# Stemma_Notecard.net
KiCad netlist of a schematic drawn in EAGLE
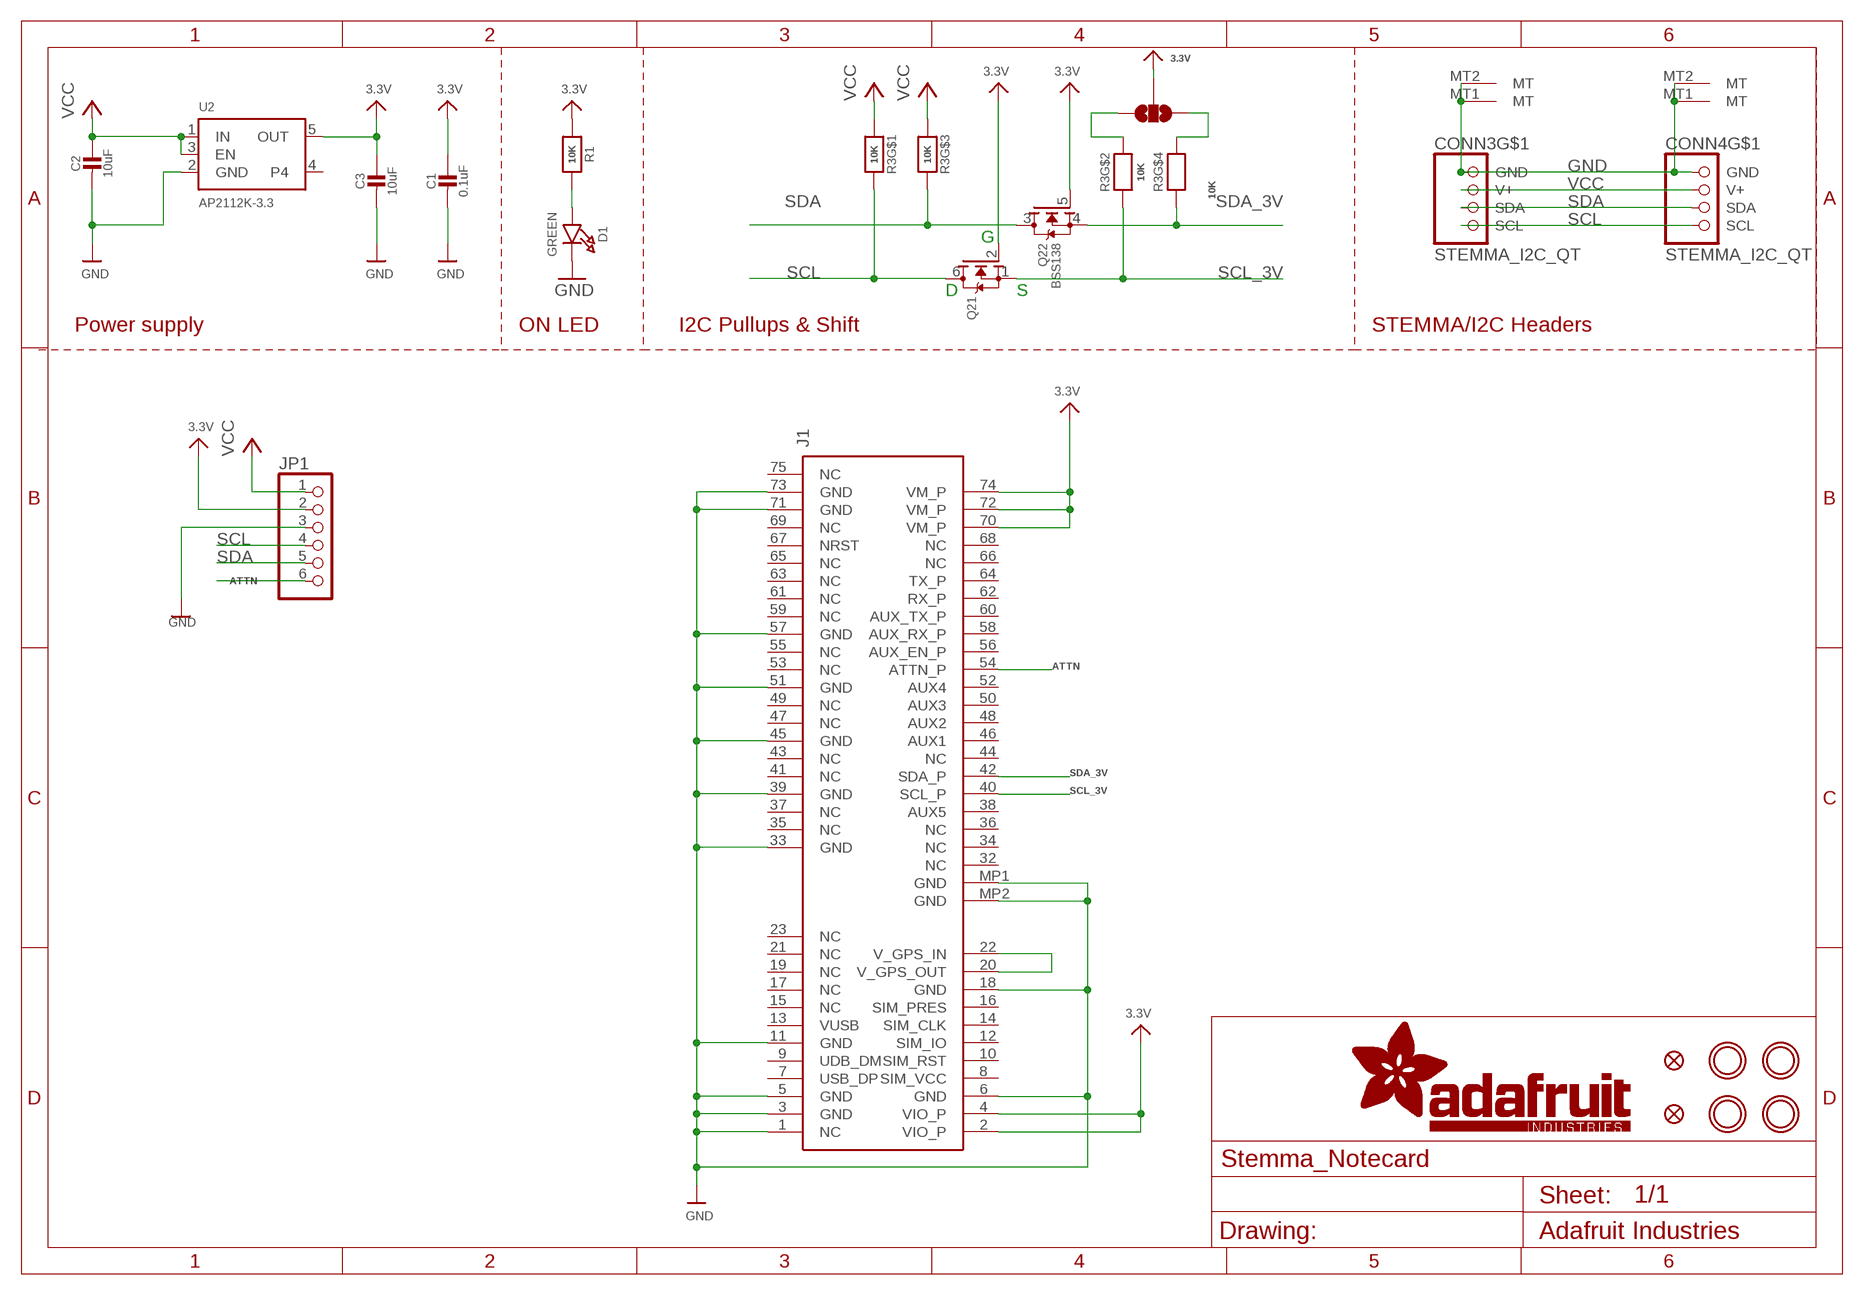
[diagram p0: schematic, sheet 1]

(export (version "E")
  (design (tool "Eeschema 10.0.6"))
  (components
    (comp (ref "C1")
      (value "0.1uF")
      (footprint "eagle-import:0603-NO")
      (libsource (lib "eagle-import") (part "CAP_CERAMIC0603_NO"))
    )
    (comp (ref "C2")
      (value "10uF")
      (footprint "eagle-import:0805-NO")
      (libsource (lib "eagle-import") (part "CAP_CERAMIC0805-NOOUTLINE"))
    )
    (comp (ref "C3")
      (value "10uF")
      (footprint "eagle-import:0805-NO")
      (libsource (lib "eagle-import") (part "CAP_CERAMIC0805-NOOUTLINE"))
    )
    (comp (ref "CONN3")
      (value "STEMMA_I2C_QT")
      (footprint "eagle-import:JST_SH4")
      (libsource (lib "eagle-import") (part "STEMMA_I2C_QT"))
    )
    (comp (ref "CONN4")
      (value "STEMMA_I2C_QT")
      (footprint "eagle-import:JST_SH4")
      (libsource (lib "eagle-import") (part "STEMMA_I2C_QT"))
    )
    (comp (ref "D1")
      (value "GREEN")
      (footprint "eagle-import:CHIPLED_0603_NOOUTLINE")
      (libsource (lib "eagle-import") (part "LED0603_NOOUTLINE"))
    )
    (comp (ref "FID3")
      (value "FIDUCIAL_1MM")
      (footprint "eagle-import:FIDUCIAL_1MM")
      (libsource (lib "eagle-import") (part "FIDUCIAL_1MM"))
    )
    (comp (ref "FID4")
      (value "FIDUCIAL_1MM")
      (footprint "eagle-import:FIDUCIAL_1MM")
      (libsource (lib "eagle-import") (part "FIDUCIAL_1MM"))
    )
    (comp (ref "J1")
      (value "MDT420E01001NOTECARD")
      (footprint "eagle-import:NOTECARD")
      (libsource (lib "eagle-import") (part "MDT420E01001NOTECARD"))
    )
    (comp (ref "JP1")
      (value "HEADER-1X670MIL")
      (footprint "eagle-import:1X06_ROUND_70")
      (libsource (lib "eagle-import") (part "HEADER-1X670MIL"))
    )
    (comp (ref "JP2")
      (value "JUMPER-SMT_3_NO_NO-SILK")
      (footprint "eagle-import:SMT-JUMPER_3_NO_NO-SILK")
      (libsource (lib "eagle-import") (part "JUMPER-SMT_3_NO_NO-SILK"))
    )
    (comp (ref "Q2")
      (value "BSS138")
      (footprint "eagle-import:SOT363")
      (libsource (lib "eagle-import") (part "MOSFET-N_DUAL"))
    )
    (comp (ref "R1")
      (value "10K")
      (footprint "eagle-import:0603-NO")
      (libsource (lib "eagle-import") (part "RESISTOR_0603_NOOUT"))
    )
    (comp (ref "R3")
      (value "10K")
      (footprint "eagle-import:RESPACK_4X0603")
      (libsource (lib "eagle-import") (part "RESISTOR_4PACK"))
    )
    (comp (ref "U$1")
      (value "MOUNTINGHOLE2.5")
      (footprint "eagle-import:MOUNTINGHOLE_2.5_PLATED")
      (libsource (lib "eagle-import") (part "MOUNTINGHOLE2.5"))
    )
    (comp (ref "U$17")
      (value "MOUNTINGHOLE2.5")
      (footprint "eagle-import:MOUNTINGHOLE_2.5_PLATED")
      (libsource (lib "eagle-import") (part "MOUNTINGHOLE2.5"))
    )
    (comp (ref "U$19")
      (value "MOUNTINGHOLE2.5")
      (footprint "eagle-import:MOUNTINGHOLE_2.5_PLATED")
      (libsource (lib "eagle-import") (part "MOUNTINGHOLE2.5"))
    )
    (comp (ref "U$21")
      (value "MOUNTINGHOLE2.5")
      (footprint "eagle-import:MOUNTINGHOLE_2.5_PLATED")
      (libsource (lib "eagle-import") (part "MOUNTINGHOLE2.5"))
    )
    (comp (ref "U2")
      (value "AP2112K-3.3")
      (footprint "eagle-import:SOT23-5")
      (libsource (lib "eagle-import") (part "VREG_SOT23-5"))
    )
  )
  (nets
    (net (code "1") (name "/SCL") (class "Default")
      (node (ref "CONN3") (pin "4") (pinfunction "SCL_4") (pintype "passive"))
      (node (ref "CONN4") (pin "4") (pinfunction "SCL_4") (pintype "passive"))
      (node (ref "JP1") (pin "4") (pinfunction "4_4") (pintype "passive"))
      (node (ref "Q2") (pin "6") (pinfunction "D_6") (pintype "bidirectional"))
      (node (ref "R3") (pin "8") (pinfunction "2_8") (pintype "passive"))
    )
    (net (code "2") (name "/SDA") (class "Default")
      (node (ref "CONN3") (pin "3") (pinfunction "SDA_3") (pintype "passive"))
      (node (ref "CONN4") (pin "3") (pinfunction "SDA_3") (pintype "passive"))
      (node (ref "JP1") (pin "5") (pinfunction "5_5") (pintype "passive"))
      (node (ref "Q2") (pin "3") (pinfunction "D_3") (pintype "bidirectional"))
      (node (ref "R3") (pin "6") (pinfunction "2_6") (pintype "passive"))
    )
    (net (code "3") (name "3.3V") (class "Default")
      (node (ref "C1") (pin "1") (pinfunction "1_1") (pintype "passive"))
      (node (ref "C3") (pin "1") (pinfunction "1_1") (pintype "passive"))
      (node (ref "J1") (pin "2") (pinfunction "VIO_P_2") (pintype "bidirectional"))
      (node (ref "J1") (pin "4") (pinfunction "VIO_P_4") (pintype "bidirectional"))
      (node (ref "J1") (pin "70") (pinfunction "VM_P_70") (pintype "bidirectional"))
      (node (ref "J1") (pin "72") (pinfunction "VM_P_72") (pintype "bidirectional"))
      (node (ref "J1") (pin "74") (pinfunction "VM_P_74") (pintype "bidirectional"))
      (node (ref "JP1") (pin "2") (pinfunction "2_2") (pintype "passive"))
      (node (ref "JP2") (pin "2") (pinfunction "2_2") (pintype "passive"))
      (node (ref "Q2") (pin "2") (pinfunction "G_2") (pintype "bidirectional"))
      (node (ref "Q2") (pin "5") (pinfunction "G_5") (pintype "bidirectional"))
      (node (ref "R1") (pin "1") (pinfunction "1_1") (pintype "passive"))
      (node (ref "U2") (pin "5") (pinfunction "OUT_5") (pintype "power_in"))
    )
    (net (code "4") (name "ATTN") (class "Default")
      (node (ref "J1") (pin "54") (pinfunction "ATTN_P_54") (pintype "bidirectional"))
      (node (ref "JP1") (pin "6") (pinfunction "6_6") (pintype "passive"))
    )
    (net (code "5") (name "GND") (class "Default")
      (node (ref "C1") (pin "2") (pinfunction "2_2") (pintype "passive"))
      (node (ref "C2") (pin "2") (pinfunction "2_2") (pintype "passive"))
      (node (ref "C3") (pin "2") (pinfunction "2_2") (pintype "passive"))
      (node (ref "CONN3") (pin "1") (pinfunction "GND_1") (pintype "passive"))
      (node (ref "CONN3") (pin "MT1") (pinfunction "MT_MT1") (pintype "bidirectional"))
      (node (ref "CONN3") (pin "MT2") (pinfunction "MT_MT2") (pintype "bidirectional"))
      (node (ref "CONN4") (pin "1") (pinfunction "GND_1") (pintype "passive"))
      (node (ref "CONN4") (pin "MT1") (pinfunction "MT_MT1") (pintype "bidirectional"))
      (node (ref "CONN4") (pin "MT2") (pinfunction "MT_MT2") (pintype "bidirectional"))
      (node (ref "D1") (pin "C") (pinfunction "C_C") (pintype "passive"))
      (node (ref "J1") (pin "1") (pinfunction "NC_1") (pintype "bidirectional"))
      (node (ref "J1") (pin "11") (pinfunction "GND_11") (pintype "bidirectional"))
      (node (ref "J1") (pin "18") (pinfunction "GND_18") (pintype "bidirectional"))
      (node (ref "J1") (pin "3") (pinfunction "GND_3") (pintype "bidirectional"))
      (node (ref "J1") (pin "33") (pinfunction "GND_33") (pintype "bidirectional"))
      (node (ref "J1") (pin "39") (pinfunction "GND_39") (pintype "bidirectional"))
      (node (ref "J1") (pin "45") (pinfunction "GND_45") (pintype "bidirectional"))
      (node (ref "J1") (pin "5") (pinfunction "GND_5") (pintype "bidirectional"))
      (node (ref "J1") (pin "51") (pinfunction "GND_51") (pintype "bidirectional"))
      (node (ref "J1") (pin "57") (pinfunction "GND_57") (pintype "bidirectional"))
      (node (ref "J1") (pin "6") (pinfunction "GND_6") (pintype "bidirectional"))
      (node (ref "J1") (pin "71") (pinfunction "GND_71") (pintype "bidirectional"))
      (node (ref "J1") (pin "73") (pinfunction "GND_73") (pintype "bidirectional"))
      (node (ref "J1") (pin "MP1") (pinfunction "GND_MP1") (pintype "power_in"))
      (node (ref "J1") (pin "MP2") (pinfunction "GND_MP2") (pintype "bidirectional"))
      (node (ref "JP1") (pin "3") (pinfunction "3_3") (pintype "passive"))
      (node (ref "U2") (pin "2") (pinfunction "GND_2") (pintype "power_in"))
    )
    (net (code "6") (name "Net-(D1-PadA)") (class "Default")
      (node (ref "D1") (pin "A") (pinfunction "A_A") (pintype "passive"))
      (node (ref "R1") (pin "2") (pinfunction "2_2") (pintype "passive"))
    )
    (net (code "7") (name "Net-(J1-V_GPS_IN)") (class "Default")
      (node (ref "J1") (pin "20") (pinfunction "V_GPS_OUT_20") (pintype "bidirectional"))
      (node (ref "J1") (pin "22") (pinfunction "V_GPS_IN_22") (pintype "bidirectional"))
    )
    (net (code "8") (name "Net-(R3B-1)") (class "Default")
      (node (ref "JP2") (pin "3") (pinfunction "3_3") (pintype "passive"))
      (node (ref "R3") (pin "2") (pinfunction "1_2") (pintype "passive"))
    )
    (net (code "9") (name "Net-(R3D-1)") (class "Default")
      (node (ref "JP2") (pin "1") (pinfunction "1_1") (pintype "passive"))
      (node (ref "R3") (pin "4") (pinfunction "1_4") (pintype "passive"))
    )
    (net (code "10") (name "SCL_3V") (class "Default")
      (node (ref "J1") (pin "40") (pinfunction "SCL_P_40") (pintype "bidirectional"))
      (node (ref "Q2") (pin "1") (pinfunction "S_1") (pintype "bidirectional"))
      (node (ref "R3") (pin "7") (pinfunction "2_7") (pintype "passive"))
    )
    (net (code "11") (name "SDA_3V") (class "Default")
      (node (ref "J1") (pin "42") (pinfunction "SDA_P_42") (pintype "bidirectional"))
      (node (ref "Q2") (pin "4") (pinfunction "S_4") (pintype "bidirectional"))
      (node (ref "R3") (pin "5") (pinfunction "2_5") (pintype "passive"))
    )
    (net (code "12") (name "VCC") (class "Default")
      (node (ref "C2") (pin "1") (pinfunction "1_1") (pintype "passive"))
      (node (ref "CONN3") (pin "2") (pinfunction "V+_2") (pintype "passive"))
      (node (ref "CONN4") (pin "2") (pinfunction "V+_2") (pintype "passive"))
      (node (ref "JP1") (pin "1") (pinfunction "1_1") (pintype "passive"))
      (node (ref "R3") (pin "1") (pinfunction "1_1") (pintype "passive"))
      (node (ref "R3") (pin "3") (pinfunction "1_3") (pintype "passive"))
      (node (ref "U2") (pin "1") (pinfunction "IN_1") (pintype "power_in"))
      (node (ref "U2") (pin "3") (pinfunction "EN_3") (pintype "input"))
    )
    (net (code "13") (name "unconnected-(J1-AUX1-Pad46)") (class "Default")
      (node (ref "J1") (pin "46") (pinfunction "AUX1_46") (pintype "bidirectional"))
    )
    (net (code "14") (name "unconnected-(J1-AUX2-Pad48)") (class "Default")
      (node (ref "J1") (pin "48") (pinfunction "AUX2_48") (pintype "bidirectional"))
    )
    (net (code "15") (name "unconnected-(J1-AUX3-Pad50)") (class "Default")
      (node (ref "J1") (pin "50") (pinfunction "AUX3_50") (pintype "bidirectional"))
    )
    (net (code "16") (name "unconnected-(J1-AUX4-Pad52)") (class "Default")
      (node (ref "J1") (pin "52") (pinfunction "AUX4_52") (pintype "bidirectional"))
    )
    (net (code "17") (name "unconnected-(J1-AUX5-Pad38)") (class "Default")
      (node (ref "J1") (pin "38") (pinfunction "AUX5_38") (pintype "bidirectional"))
    )
    (net (code "18") (name "unconnected-(J1-AUX_EN_P-Pad56)") (class "Default")
      (node (ref "J1") (pin "56") (pinfunction "AUX_EN_P_56") (pintype "bidirectional"))
    )
    (net (code "19") (name "unconnected-(J1-AUX_RX_P-Pad58)") (class "Default")
      (node (ref "J1") (pin "58") (pinfunction "AUX_RX_P_58") (pintype "bidirectional"))
    )
    (net (code "20") (name "unconnected-(J1-AUX_TX_P-Pad60)") (class "Default")
      (node (ref "J1") (pin "60") (pinfunction "AUX_TX_P_60") (pintype "bidirectional"))
    )
    (net (code "21") (name "unconnected-(J1-NC-Pad15)") (class "Default")
      (node (ref "J1") (pin "15") (pinfunction "NC_15") (pintype "bidirectional"))
    )
    (net (code "22") (name "unconnected-(J1-NC-Pad17)") (class "Default")
      (node (ref "J1") (pin "17") (pinfunction "NC_17") (pintype "bidirectional"))
    )
    (net (code "23") (name "unconnected-(J1-NC-Pad19)") (class "Default")
      (node (ref "J1") (pin "19") (pinfunction "NC_19") (pintype "bidirectional"))
    )
    (net (code "24") (name "unconnected-(J1-NC-Pad21)") (class "Default")
      (node (ref "J1") (pin "21") (pinfunction "NC_21") (pintype "bidirectional"))
    )
    (net (code "25") (name "unconnected-(J1-NC-Pad23)") (class "Default")
      (node (ref "J1") (pin "23") (pinfunction "NC_23") (pintype "bidirectional"))
    )
    (net (code "26") (name "unconnected-(J1-NC-Pad32)") (class "Default")
      (node (ref "J1") (pin "32") (pinfunction "NC_32") (pintype "bidirectional"))
    )
    (net (code "27") (name "unconnected-(J1-NC-Pad34)") (class "Default")
      (node (ref "J1") (pin "34") (pinfunction "NC_34") (pintype "bidirectional"))
    )
    (net (code "28") (name "unconnected-(J1-NC-Pad35)") (class "Default")
      (node (ref "J1") (pin "35") (pinfunction "NC_35") (pintype "bidirectional"))
    )
    (net (code "29") (name "unconnected-(J1-NC-Pad36)") (class "Default")
      (node (ref "J1") (pin "36") (pinfunction "NC_36") (pintype "bidirectional"))
    )
    (net (code "30") (name "unconnected-(J1-NC-Pad37)") (class "Default")
      (node (ref "J1") (pin "37") (pinfunction "NC_37") (pintype "bidirectional"))
    )
    (net (code "31") (name "unconnected-(J1-NC-Pad41)") (class "Default")
      (node (ref "J1") (pin "41") (pinfunction "NC_41") (pintype "bidirectional"))
    )
    (net (code "32") (name "unconnected-(J1-NC-Pad43)") (class "Default")
      (node (ref "J1") (pin "43") (pinfunction "NC_43") (pintype "bidirectional"))
    )
    (net (code "33") (name "unconnected-(J1-NC-Pad44)") (class "Default")
      (node (ref "J1") (pin "44") (pinfunction "NC_44") (pintype "bidirectional"))
    )
    (net (code "34") (name "unconnected-(J1-NC-Pad47)") (class "Default")
      (node (ref "J1") (pin "47") (pinfunction "NC_47") (pintype "bidirectional"))
    )
    (net (code "35") (name "unconnected-(J1-NC-Pad49)") (class "Default")
      (node (ref "J1") (pin "49") (pinfunction "NC_49") (pintype "bidirectional"))
    )
    (net (code "36") (name "unconnected-(J1-NC-Pad53)") (class "Default")
      (node (ref "J1") (pin "53") (pinfunction "NC_53") (pintype "bidirectional"))
    )
    (net (code "37") (name "unconnected-(J1-NC-Pad55)") (class "Default")
      (node (ref "J1") (pin "55") (pinfunction "NC_55") (pintype "bidirectional"))
    )
    (net (code "38") (name "unconnected-(J1-NC-Pad59)") (class "Default")
      (node (ref "J1") (pin "59") (pinfunction "NC_59") (pintype "bidirectional"))
    )
    (net (code "39") (name "unconnected-(J1-NC-Pad61)") (class "Default")
      (node (ref "J1") (pin "61") (pinfunction "NC_61") (pintype "bidirectional"))
    )
    (net (code "40") (name "unconnected-(J1-NC-Pad63)") (class "Default")
      (node (ref "J1") (pin "63") (pinfunction "NC_63") (pintype "bidirectional"))
    )
    (net (code "41") (name "unconnected-(J1-NC-Pad65)") (class "Default")
      (node (ref "J1") (pin "65") (pinfunction "NC_65") (pintype "bidirectional"))
    )
    (net (code "42") (name "unconnected-(J1-NC-Pad66)") (class "Default")
      (node (ref "J1") (pin "66") (pinfunction "NC_66") (pintype "bidirectional"))
    )
    (net (code "43") (name "unconnected-(J1-NC-Pad68)") (class "Default")
      (node (ref "J1") (pin "68") (pinfunction "NC_68") (pintype "bidirectional"))
    )
    (net (code "44") (name "unconnected-(J1-NC-Pad69)") (class "Default")
      (node (ref "J1") (pin "69") (pinfunction "NC_69") (pintype "bidirectional"))
    )
    (net (code "45") (name "unconnected-(J1-NC-Pad75)") (class "Default")
      (node (ref "J1") (pin "75") (pinfunction "NC_75") (pintype "bidirectional"))
    )
    (net (code "46") (name "unconnected-(J1-NRST-Pad67)") (class "Default")
      (node (ref "J1") (pin "67") (pinfunction "NRST_67") (pintype "bidirectional"))
    )
    (net (code "47") (name "unconnected-(J1-RX_P-Pad62)") (class "Default")
      (node (ref "J1") (pin "62") (pinfunction "RX_P_62") (pintype "bidirectional"))
    )
    (net (code "48") (name "unconnected-(J1-SIM_CLK-Pad14)") (class "Default")
      (node (ref "J1") (pin "14") (pinfunction "SIM_CLK_14") (pintype "bidirectional"))
    )
    (net (code "49") (name "unconnected-(J1-SIM_IO-Pad12)") (class "Default")
      (node (ref "J1") (pin "12") (pinfunction "SIM_IO_12") (pintype "bidirectional"))
    )
    (net (code "50") (name "unconnected-(J1-SIM_PRES-Pad16)") (class "Default")
      (node (ref "J1") (pin "16") (pinfunction "SIM_PRES_16") (pintype "bidirectional"))
    )
    (net (code "51") (name "unconnected-(J1-SIM_RST-Pad10)") (class "Default")
      (node (ref "J1") (pin "10") (pinfunction "SIM_RST_10") (pintype "bidirectional"))
    )
    (net (code "52") (name "unconnected-(J1-SIM_VCC-Pad8)") (class "Default")
      (node (ref "J1") (pin "8") (pinfunction "SIM_VCC_8") (pintype "bidirectional"))
    )
    (net (code "53") (name "unconnected-(J1-TX_P-Pad64)") (class "Default")
      (node (ref "J1") (pin "64") (pinfunction "TX_P_64") (pintype "bidirectional"))
    )
    (net (code "54") (name "unconnected-(J1-UDB_DM-Pad9)") (class "Default")
      (node (ref "J1") (pin "9") (pinfunction "UDB_DM_9") (pintype "bidirectional"))
    )
    (net (code "55") (name "unconnected-(J1-USB_DP-Pad7)") (class "Default")
      (node (ref "J1") (pin "7") (pinfunction "USB_DP_7") (pintype "bidirectional"))
    )
    (net (code "56") (name "unconnected-(J1-VUSB-Pad13)") (class "Default")
      (node (ref "J1") (pin "13") (pinfunction "VUSB_13") (pintype "bidirectional"))
    )
    (net (code "57") (name "unconnected-(U2-P4-Pad4)") (class "Default")
      (node (ref "U2") (pin "4") (pinfunction "P4_4") (pintype "bidirectional"))
    )
  )
)
